# Sheet1.net
KiCad netlist of a schematic drawn in Altium Designer
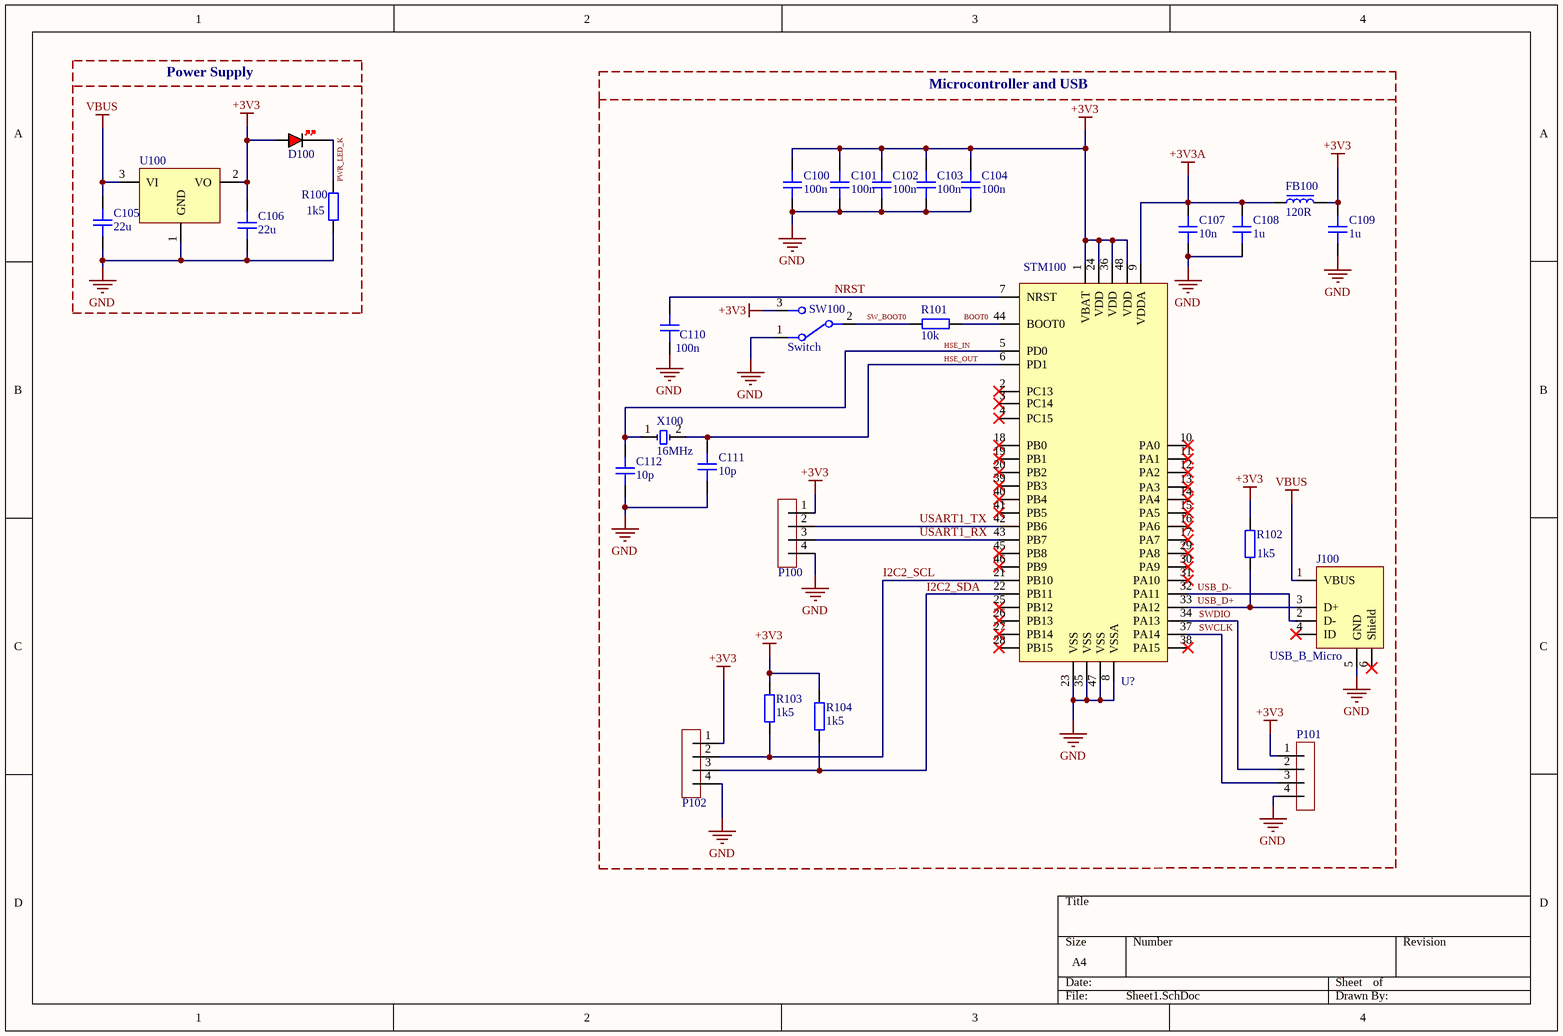
[diagram p0: Sheet1.SchDoc]

(export (version "E")
  (design (tool "Eeschema 10.0.6"))
  (components
    (comp (ref "C100")
      (value "100n")
      (footprint "CAP_0603")
      (description "Capacitor SMD 0603 10V")
      (libsource (lib "Schematic-Lib-Zhrzkn") (part "CAP_0603_10V"))
    )
    (comp (ref "C101")
      (value "100n")
      (footprint "CAP_0603")
      (description "Capacitor SMD 0603 10V")
      (libsource (lib "Schematic-Lib-Zhrzkn") (part "CAP_0603_10V"))
    )
    (comp (ref "C102")
      (value "100n")
      (footprint "CAP_0603")
      (description "Capacitor SMD 0603 10V")
      (libsource (lib "Schematic-Lib-Zhrzkn") (part "CAP_0603_10V"))
    )
    (comp (ref "C103")
      (value "100n")
      (footprint "CAP_0603")
      (description "Capacitor SMD 0603 10V")
      (libsource (lib "Schematic-Lib-Zhrzkn") (part "CAP_0603_10V"))
    )
    (comp (ref "C104")
      (value "100n")
      (footprint "CAP_0603")
      (description "Capacitor SMD 0603 10V")
      (libsource (lib "Schematic-Lib-Zhrzkn") (part "CAP_0603_10V"))
    )
    (comp (ref "C105")
      (value "22u")
      (footprint "CAP_0603")
      (description "Capacitor SMD 0603 10V")
      (libsource (lib "Schematic-Lib-Zhrzkn") (part "CAP_0603_10V"))
    )
    (comp (ref "C106")
      (value "22u")
      (footprint "CAP_0603")
      (description "Capacitor SMD 0603 10V")
      (libsource (lib "Schematic-Lib-Zhrzkn") (part "CAP_0603_10V"))
    )
    (comp (ref "C107")
      (value "10n")
      (footprint "CAP_0603")
      (description "Capacitor SMD 0603 10V")
      (libsource (lib "Schematic-Lib-Zhrzkn") (part "CAP_0603_10V"))
    )
    (comp (ref "C108")
      (value "1u")
      (footprint "CAP_0603")
      (description "Capacitor SMD 0603 10V")
      (libsource (lib "Schematic-Lib-Zhrzkn") (part "CAP_0603_10V"))
    )
    (comp (ref "C109")
      (value "1u")
      (footprint "CAP_0603")
      (description "Capacitor SMD 0603 10V")
      (libsource (lib "Schematic-Lib-Zhrzkn") (part "CAP_0603_10V"))
    )
    (comp (ref "C110")
      (value "100n")
      (footprint "CAP_0603")
      (description "Capacitor SMD 0603 10V")
      (libsource (lib "Schematic-Lib-Zhrzkn") (part "CAP_0603_10V"))
    )
    (comp (ref "C111")
      (value "10p")
      (footprint "CAP_0603")
      (description "Capacitor SMD 0603 10V")
      (libsource (lib "Schematic-Lib-Zhrzkn") (part "CAP_0603_10V"))
    )
    (comp (ref "C112")
      (value "10p")
      (footprint "CAP_0603")
      (description "Capacitor SMD 0603 10V")
      (libsource (lib "Schematic-Lib-Zhrzkn") (part "CAP_0603_10V"))
    )
    (comp (ref "D100")
      (value "RED")
      (footprint "LED_0603_RED")
      (description "LED 0603 RED SMD")
      (libsource (lib "Schematic-Lib-Zhrzkn") (part "LED_0603_RED"))
    )
    (comp (ref "FB100")
      (value "120R")
      (footprint "FB_0603")
      (description "Ferrite Bead SMD 0603")
      (libsource (lib "Schematic-Lib-Zhrzkn") (part "FB_0603"))
    )
    (comp (ref "J100")
      (value "USB_B_Micro")
      (footprint "USB_B_MICRO")
      (libsource (lib "Schematic-Lib-Zhrzkn") (part "USB_B_Micro"))
    )
    (comp (ref "P100")
      (value "Terminal_Block_Header_1")
      (footprint "HEADER_4")
      (description "4 pin Male")
      (libsource (lib "Schematic-Lib-Zhrzkn") (part "Terminal_Block_Header_1"))
    )
    (comp (ref "P101")
      (value "Terminal_Block_Header_1")
      (footprint "HEADER_4")
      (description "4 pin Male")
      (libsource (lib "") (part "Terminal_Block_Header_1_1"))
    )
    (comp (ref "P102")
      (value "Terminal_Block_Header_1")
      (footprint "HEADER_4")
      (description "4 pin Male")
      (libsource (lib "Schematic-Lib-Zhrzkn") (part "Terminal_Block_Header_1"))
    )
    (comp (ref "R100")
      (value "1k5")
      (footprint "RES_0603")
      (description "Resistor SMD 0603")
      (libsource (lib "Schematic-Lib-Zhrzkn") (part "RES_0603"))
    )
    (comp (ref "R101")
      (value "10k")
      (footprint "RES_0603")
      (description "Resistor SMD 0603")
      (libsource (lib "Schematic-Lib-Zhrzkn") (part "RES_0603"))
    )
    (comp (ref "R102")
      (value "1k5")
      (footprint "RES_0603")
      (description "Resistor SMD 0603")
      (libsource (lib "Schematic-Lib-Zhrzkn") (part "RES_0603"))
    )
    (comp (ref "R103")
      (value "1k5")
      (footprint "RES_0603")
      (description "Resistor SMD 0603")
      (libsource (lib "Schematic-Lib-Zhrzkn") (part "RES_0603"))
    )
    (comp (ref "R104")
      (value "1k5")
      (footprint "RES_0603")
      (description "Resistor SMD 0603")
      (libsource (lib "Schematic-Lib-Zhrzkn") (part "RES_0603"))
    )
    (comp (ref "STM100")
      (value "U?")
      (footprint "STM32F103C8TX")
      (description "IC MCU 32BIT 64KB FLASH 48LQFP")
      (fields
        (field (name "MANUFACTURER") "STMicroelectronics")
        (field (name "MANUFACTURER PART NUMBER") "STM32F103C8T6")
      )
      (libsource (lib "Schematic-Lib-Zhrzkn") (part "STM32F103C8TX"))
    )
    (comp (ref "SW100")
      (value "Switch")
      (footprint "SWITCH")
      (libsource (lib "Schematic-Lib-Zhrzkn") (part "Switch"))
    )
    (comp (ref "U100")
      (value "Linear Voltage Regulator")
      (footprint "AMS1117")
      (description "IC-1117 V.REG. 1A 3V3 SOT223 SMD AMS")
      (libsource (lib "Schematic-Lib-Zhrzkn") (part "AMS1117"))
    )
    (comp (ref "X100")
      (value "16MHz")
      (footprint "Crystal 8MHZ")
      (description "16MHz SMD Crystal Resonator 10pF ±10ppm ±30ppm -40℃~+85℃ SMD3225-4P Crystals ROHS")
      (fields
        (field (name "MANUFACTURER") "Abracon")
        (field (name "MANUFACTURER PART NUMBER") "ABLS-8.000MHZ-B4-T")
      )
      (libsource (lib "Schematic-Lib-Zhrzkn") (part "Crystal 8MHz"))
    )
  )
  (nets
    (net (code "1") (name "+3V3") (class "Default")
      (node (ref "C100") (pin "2") (pinfunction "2_2") (pintype "passive"))
      (node (ref "C101") (pin "2") (pinfunction "2_2") (pintype "passive"))
      (node (ref "C102") (pin "2") (pinfunction "2_2") (pintype "passive"))
      (node (ref "C103") (pin "2") (pinfunction "2_2") (pintype "passive"))
      (node (ref "C104") (pin "2") (pinfunction "2_2") (pintype "passive"))
      (node (ref "C106") (pin "2") (pinfunction "2_2") (pintype "passive"))
      (node (ref "C109") (pin "2") (pinfunction "2_2") (pintype "passive"))
      (node (ref "D100") (pin "A") (pinfunction "A_A") (pintype "passive"))
      (node (ref "FB100") (pin "2") (pinfunction "2_2") (pintype "passive"))
      (node (ref "P100") (pin "1") (pintype "passive"))
      (node (ref "P101") (pin "1") (pintype "passive"))
      (node (ref "P102") (pin "1") (pintype "passive"))
      (node (ref "R102") (pin "2") (pinfunction "2_2") (pintype "passive"))
      (node (ref "R103") (pin "2") (pinfunction "2_2") (pintype "passive"))
      (node (ref "R104") (pin "2") (pinfunction "2_2") (pintype "passive"))
      (node (ref "STM100") (pin "1") (pinfunction "VBAT_1") (pintype "passive"))
      (node (ref "STM100") (pin "24") (pinfunction "VDD_24") (pintype "passive"))
      (node (ref "STM100") (pin "36") (pinfunction "VDD_36") (pintype "passive"))
      (node (ref "STM100") (pin "48") (pinfunction "VDD_48") (pintype "passive"))
      (node (ref "SW100") (pin "3") (pinfunction "3_3") (pintype "passive"))
      (node (ref "U100") (pin "2") (pinfunction "VO_2") (pintype "passive"))
    )
    (net (code "2") (name "+3V3A") (class "Default")
      (node (ref "C107") (pin "2") (pinfunction "2_2") (pintype "passive"))
      (node (ref "C108") (pin "2") (pinfunction "2_2") (pintype "passive"))
      (node (ref "FB100") (pin "1") (pinfunction "1_1") (pintype "passive"))
      (node (ref "STM100") (pin "9") (pinfunction "VDDA_9") (pintype "passive"))
    )
    (net (code "4") (name "/HSE_IN") (class "Default")
      (node (ref "C112") (pin "2") (pinfunction "2_2") (pintype "passive"))
      (node (ref "STM100") (pin "5") (pinfunction "PD0_5") (pintype "passive"))
      (node (ref "X100") (pin "1") (pintype "passive"))
    )
    (net (code "5") (name "/HSE_OUT") (class "Default")
      (node (ref "C111") (pin "2") (pinfunction "2_2") (pintype "passive"))
      (node (ref "STM100") (pin "6") (pinfunction "PD1_6") (pintype "passive"))
      (node (ref "X100") (pin "2") (pintype "passive"))
    )
    (net (code "6") (name "/I2C2_SCL") (class "Default")
      (node (ref "P102") (pin "2") (pintype "passive"))
      (node (ref "R103") (pin "1") (pinfunction "1_1") (pintype "passive"))
      (node (ref "STM100") (pin "21") (pinfunction "PB10_21") (pintype "passive"))
    )
    (net (code "7") (name "/I2C2_SDA") (class "Default")
      (node (ref "P102") (pin "3") (pintype "passive"))
      (node (ref "R104") (pin "1") (pinfunction "1_1") (pintype "passive"))
      (node (ref "STM100") (pin "22") (pinfunction "PB11_22") (pintype "passive"))
    )
    (net (code "8") (name "/NRST") (class "Default")
      (node (ref "C110") (pin "2") (pinfunction "2_2") (pintype "passive"))
      (node (ref "STM100") (pin "7") (pinfunction "NRST_7") (pintype "passive"))
    )
    (net (code "10") (name "/SWCLK") (class "Default")
      (node (ref "P101") (pin "3") (pintype "passive"))
      (node (ref "STM100") (pin "37") (pinfunction "PA14_37") (pintype "passive"))
    )
    (net (code "11") (name "/SWDIO") (class "Default")
      (node (ref "P101") (pin "2") (pintype "passive"))
      (node (ref "STM100") (pin "34") (pinfunction "PA13_34") (pintype "passive"))
    )
    (net (code "13") (name "/USART1_RX") (class "Default")
      (node (ref "P100") (pin "3") (pintype "passive"))
      (node (ref "STM100") (pin "43") (pinfunction "PB7_43") (pintype "passive"))
    )
    (net (code "14") (name "/USART1_TX") (class "Default")
      (node (ref "P100") (pin "2") (pintype "passive"))
      (node (ref "STM100") (pin "42") (pinfunction "PB6_42") (pintype "passive"))
    )
    (net (code "15") (name "/USB_D+") (class "Default")
      (node (ref "J100") (pin "3") (pinfunction "D+_3") (pintype "passive"))
      (node (ref "R102") (pin "1") (pinfunction "1_1") (pintype "passive"))
      (node (ref "STM100") (pin "33") (pinfunction "PA12_33") (pintype "passive"))
    )
    (net (code "16") (name "/USB_D-") (class "Default")
      (node (ref "J100") (pin "2") (pinfunction "D-_2") (pintype "passive"))
      (node (ref "STM100") (pin "32") (pinfunction "PA11_32") (pintype "passive"))
    )
    (net (code "17") (name "GND") (class "Default")
      (node (ref "C100") (pin "1") (pinfunction "1_1") (pintype "passive"))
      (node (ref "C101") (pin "1") (pinfunction "1_1") (pintype "passive"))
      (node (ref "C102") (pin "1") (pinfunction "1_1") (pintype "passive"))
      (node (ref "C103") (pin "1") (pinfunction "1_1") (pintype "passive"))
      (node (ref "C104") (pin "1") (pinfunction "1_1") (pintype "passive"))
      (node (ref "C105") (pin "1") (pinfunction "1_1") (pintype "passive"))
      (node (ref "C106") (pin "1") (pinfunction "1_1") (pintype "passive"))
      (node (ref "C107") (pin "1") (pinfunction "1_1") (pintype "passive"))
      (node (ref "C108") (pin "1") (pinfunction "1_1") (pintype "passive"))
      (node (ref "C109") (pin "1") (pinfunction "1_1") (pintype "passive"))
      (node (ref "C110") (pin "1") (pinfunction "1_1") (pintype "passive"))
      (node (ref "C111") (pin "1") (pinfunction "1_1") (pintype "passive"))
      (node (ref "C112") (pin "1") (pinfunction "1_1") (pintype "passive"))
      (node (ref "J100") (pin "5") (pinfunction "GND_5") (pintype "passive"))
      (node (ref "P100") (pin "4") (pintype "passive"))
      (node (ref "P101") (pin "4") (pintype "passive"))
      (node (ref "P102") (pin "4") (pintype "passive"))
      (node (ref "R100") (pin "1") (pinfunction "1_1") (pintype "passive"))
      (node (ref "STM100") (pin "23") (pinfunction "VSS_23") (pintype "passive"))
      (node (ref "STM100") (pin "35") (pinfunction "VSS_35") (pintype "passive"))
      (node (ref "STM100") (pin "47") (pinfunction "VSS_47") (pintype "passive"))
      (node (ref "STM100") (pin "8") (pinfunction "VSSA_8") (pintype "passive"))
      (node (ref "SW100") (pin "1") (pinfunction "1_1") (pintype "passive"))
      (node (ref "U100") (pin "1") (pinfunction "GND_1") (pintype "passive"))
    )
    (net (code "18") (name "Net-(D100-PadK)") (class "Default")
      (node (ref "D100") (pin "K") (pinfunction "K_K") (pintype "passive"))
      (node (ref "R100") (pin "2") (pinfunction "2_2") (pintype "passive"))
    )
    (net (code "19") (name "Net-(STM100-BOOT0)") (class "Default")
      (node (ref "R101") (pin "2") (pinfunction "2_2") (pintype "passive"))
      (node (ref "STM100") (pin "44") (pinfunction "BOOT0_44") (pintype "passive"))
    )
    (net (code "20") (name "Net-(SW100-COM)") (class "Default")
      (node (ref "R101") (pin "1") (pinfunction "1_1") (pintype "passive"))
      (node (ref "SW100") (pin "2") (pinfunction "COM_2") (pintype "passive"))
    )
    (net (code "21") (name "VBUS") (class "Default")
      (node (ref "C105") (pin "2") (pinfunction "2_2") (pintype "passive"))
      (node (ref "J100") (pin "1") (pinfunction "VBUS_1") (pintype "passive"))
      (node (ref "U100") (pin "3") (pinfunction "VI_3") (pintype "passive"))
    )
    (net (code "22") (name "unconnected-(J100-ID-Pad4)") (class "Default")
      (node (ref "J100") (pin "4") (pinfunction "ID_4") (pintype "passive+no_connect"))
    )
    (net (code "23") (name "unconnected-(J100-Shield-Pad6)") (class "Default")
      (node (ref "J100") (pin "6") (pinfunction "Shield_6") (pintype "passive+no_connect"))
    )
    (net (code "24") (name "unconnected-(STM100-PA0-Pad10)") (class "Default")
      (node (ref "STM100") (pin "10") (pinfunction "PA0_10") (pintype "passive+no_connect"))
    )
    (net (code "25") (name "unconnected-(STM100-PA1-Pad11)") (class "Default")
      (node (ref "STM100") (pin "11") (pinfunction "PA1_11") (pintype "passive+no_connect"))
    )
    (net (code "26") (name "unconnected-(STM100-PA2-Pad12)") (class "Default")
      (node (ref "STM100") (pin "12") (pinfunction "PA2_12") (pintype "passive+no_connect"))
    )
    (net (code "27") (name "unconnected-(STM100-PA3-Pad13)") (class "Default")
      (node (ref "STM100") (pin "13") (pinfunction "PA3_13") (pintype "passive+no_connect"))
    )
    (net (code "28") (name "unconnected-(STM100-PA4-Pad14)") (class "Default")
      (node (ref "STM100") (pin "14") (pinfunction "PA4_14") (pintype "passive+no_connect"))
    )
    (net (code "29") (name "unconnected-(STM100-PA5-Pad15)") (class "Default")
      (node (ref "STM100") (pin "15") (pinfunction "PA5_15") (pintype "passive+no_connect"))
    )
    (net (code "30") (name "unconnected-(STM100-PA6-Pad16)") (class "Default")
      (node (ref "STM100") (pin "16") (pinfunction "PA6_16") (pintype "passive+no_connect"))
    )
    (net (code "31") (name "unconnected-(STM100-PA7-Pad17)") (class "Default")
      (node (ref "STM100") (pin "17") (pinfunction "PA7_17") (pintype "passive+no_connect"))
    )
    (net (code "32") (name "unconnected-(STM100-PA8-Pad29)") (class "Default")
      (node (ref "STM100") (pin "29") (pinfunction "PA8_29") (pintype "passive+no_connect"))
    )
    (net (code "33") (name "unconnected-(STM100-PA9-Pad30)") (class "Default")
      (node (ref "STM100") (pin "30") (pinfunction "PA9_30") (pintype "passive+no_connect"))
    )
    (net (code "34") (name "unconnected-(STM100-PA10-Pad31)") (class "Default")
      (node (ref "STM100") (pin "31") (pinfunction "PA10_31") (pintype "passive+no_connect"))
    )
    (net (code "35") (name "unconnected-(STM100-PA15-Pad38)") (class "Default")
      (node (ref "STM100") (pin "38") (pinfunction "PA15_38") (pintype "passive+no_connect"))
    )
    (net (code "36") (name "unconnected-(STM100-PB0-Pad18)") (class "Default")
      (node (ref "STM100") (pin "18") (pinfunction "PB0_18") (pintype "passive+no_connect"))
    )
    (net (code "37") (name "unconnected-(STM100-PB1-Pad19)") (class "Default")
      (node (ref "STM100") (pin "19") (pinfunction "PB1_19") (pintype "passive+no_connect"))
    )
    (net (code "38") (name "unconnected-(STM100-PB2-Pad20)") (class "Default")
      (node (ref "STM100") (pin "20") (pinfunction "PB2_20") (pintype "passive+no_connect"))
    )
    (net (code "39") (name "unconnected-(STM100-PB3-Pad39)") (class "Default")
      (node (ref "STM100") (pin "39") (pinfunction "PB3_39") (pintype "passive+no_connect"))
    )
    (net (code "40") (name "unconnected-(STM100-PB4-Pad40)") (class "Default")
      (node (ref "STM100") (pin "40") (pinfunction "PB4_40") (pintype "passive+no_connect"))
    )
    (net (code "41") (name "unconnected-(STM100-PB5-Pad41)") (class "Default")
      (node (ref "STM100") (pin "41") (pinfunction "PB5_41") (pintype "passive+no_connect"))
    )
    (net (code "42") (name "unconnected-(STM100-PB8-Pad45)") (class "Default")
      (node (ref "STM100") (pin "45") (pinfunction "PB8_45") (pintype "passive+no_connect"))
    )
    (net (code "43") (name "unconnected-(STM100-PB9-Pad46)") (class "Default")
      (node (ref "STM100") (pin "46") (pinfunction "PB9_46") (pintype "passive+no_connect"))
    )
    (net (code "44") (name "unconnected-(STM100-PB12-Pad25)") (class "Default")
      (node (ref "STM100") (pin "25") (pinfunction "PB12_25") (pintype "passive+no_connect"))
    )
    (net (code "45") (name "unconnected-(STM100-PB13-Pad26)") (class "Default")
      (node (ref "STM100") (pin "26") (pinfunction "PB13_26") (pintype "passive+no_connect"))
    )
    (net (code "46") (name "unconnected-(STM100-PB14-Pad27)") (class "Default")
      (node (ref "STM100") (pin "27") (pinfunction "PB14_27") (pintype "passive+no_connect"))
    )
    (net (code "47") (name "unconnected-(STM100-PB15-Pad28)") (class "Default")
      (node (ref "STM100") (pin "28") (pinfunction "PB15_28") (pintype "passive+no_connect"))
    )
    (net (code "48") (name "unconnected-(STM100-PC13-Pad2)") (class "Default")
      (node (ref "STM100") (pin "2") (pinfunction "PC13_2") (pintype "passive+no_connect"))
    )
    (net (code "49") (name "unconnected-(STM100-PC14-Pad3)") (class "Default")
      (node (ref "STM100") (pin "3") (pinfunction "PC14_3") (pintype "passive+no_connect"))
    )
    (net (code "50") (name "unconnected-(STM100-PC15-Pad4)") (class "Default")
      (node (ref "STM100") (pin "4") (pinfunction "PC15_4") (pintype "passive+no_connect"))
    )
  )
)
